# LED_Feedback.net
KiCad netlist of a schematic drawn in Altium Designer
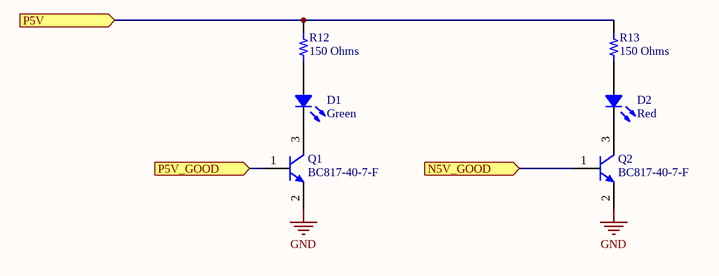
[diagram p0: LED_Feedback.SchDoc]

(export (version "E")
  (design (tool "Eeschema 10.0.6"))
  (components
    (comp (ref "D1")
      (value "Green")
      (footprint "LED 0805_2012 GREEN")
      (description "LED GREEN DIFFUSED 0805 SMD")
      (fields
        (field (name "PART NUMBER") "CMD17-21VGD/TR8")
        (field (name "MANUFACTURER") "Visual Communications Company - VCC")
      )
      (libsource (lib "Celestial Altium Library - altium_library") (part "LED"))
    )
    (comp (ref "D2")
      (value "Red")
      (footprint "LED 0805_2012 RED")
      (description "LED RED DIFFUSED 0805 SMD")
      (fields
        (field (name "PART NUMBER") "CMD17-21VRD/TR8")
        (field (name "MANUFACTURER") "Visual Communications Company - VCC")
      )
      (libsource (lib "Celestial Altium Library - altium_library") (part "LED"))
    )
    (comp (ref "Q1")
      (value "BC817-40-7-F")
      (footprint "DIODES SOT-23-3")
      (description "TRANS NPN 45V 0.5A SOT23-3")
      (fields (field (name "MANUFACTURER") "Diodes Incorporated"))
      (libsource (lib "Celestial Altium Library - altium_library") (part "DIODES INC NPN SOT-23-3"))
    )
    (comp (ref "Q2")
      (value "BC817-40-7-F")
      (footprint "DIODES SOT-23-3")
      (description "TRANS NPN 45V 0.5A SOT23-3")
      (fields (field (name "MANUFACTURER") "Diodes Incorporated"))
      (libsource (lib "Celestial Altium Library - altium_library") (part "DIODES INC NPN SOT-23-3"))
    )
    (comp (ref "R12")
      (value "150 Ohms")
      (footprint "RES 1206_3216")
      (description "RES SMD 150 OHM 1% 1/4W 1206")
      (fields (field (name "PART NUMBER") "RT1206FRE07150RL") (field (name "MANUFACTURER") "Yageo"))
      (libsource (lib "Celestial Altium Library - altium_library") (part "Resistor"))
    )
    (comp (ref "R13")
      (value "150 Ohms")
      (footprint "RES 1206_3216")
      (description "RES SMD 150 OHM 1% 1/4W 1206")
      (fields (field (name "PART NUMBER") "RT1206FRE07150RL") (field (name "MANUFACTURER") "Yageo"))
      (libsource (lib "Celestial Altium Library - altium_library") (part "Resistor"))
    )
  )
  (nets
    (net (code "1") (name "/N5V_GOOD") (class "Default")
      (node (ref "Q2") (pin "1") (pinfunction "B_1") (pintype "passive"))
    )
    (net (code "2") (name "/P5V") (class "Default")
      (node (ref "R12") (pin "2") (pinfunction "2_2") (pintype "passive"))
      (node (ref "R13") (pin "2") (pinfunction "2_2") (pintype "passive"))
    )
    (net (code "3") (name "/P5V_GOOD") (class "Default")
      (node (ref "Q1") (pin "1") (pinfunction "B_1") (pintype "passive"))
    )
    (net (code "4") (name "GND") (class "Default")
      (node (ref "Q1") (pin "2") (pinfunction "E_2") (pintype "passive"))
      (node (ref "Q2") (pin "2") (pinfunction "E_2") (pintype "passive"))
    )
    (net (code "5") (name "Net-(D1-Pad1)") (class "Default")
      (node (ref "D1") (pin "1") (pinfunction "1_1") (pintype "passive"))
      (node (ref "R12") (pin "1") (pinfunction "1_1") (pintype "passive"))
    )
    (net (code "6") (name "Net-(D2-Pad1)") (class "Default")
      (node (ref "D2") (pin "1") (pinfunction "1_1") (pintype "passive"))
      (node (ref "R13") (pin "1") (pinfunction "1_1") (pintype "passive"))
    )
    (net (code "7") (name "Net-(Q1-C)") (class "Default")
      (node (ref "D1") (pin "2") (pinfunction "2_2") (pintype "passive"))
      (node (ref "Q1") (pin "3") (pinfunction "C_3") (pintype "passive"))
    )
    (net (code "8") (name "Net-(Q2-C)") (class "Default")
      (node (ref "D2") (pin "2") (pinfunction "2_2") (pintype "passive"))
      (node (ref "Q2") (pin "3") (pinfunction "C_3") (pintype "passive"))
    )
  )
)
